# R284A.net
KiCad netlist of a schematic drawn in EAGLE
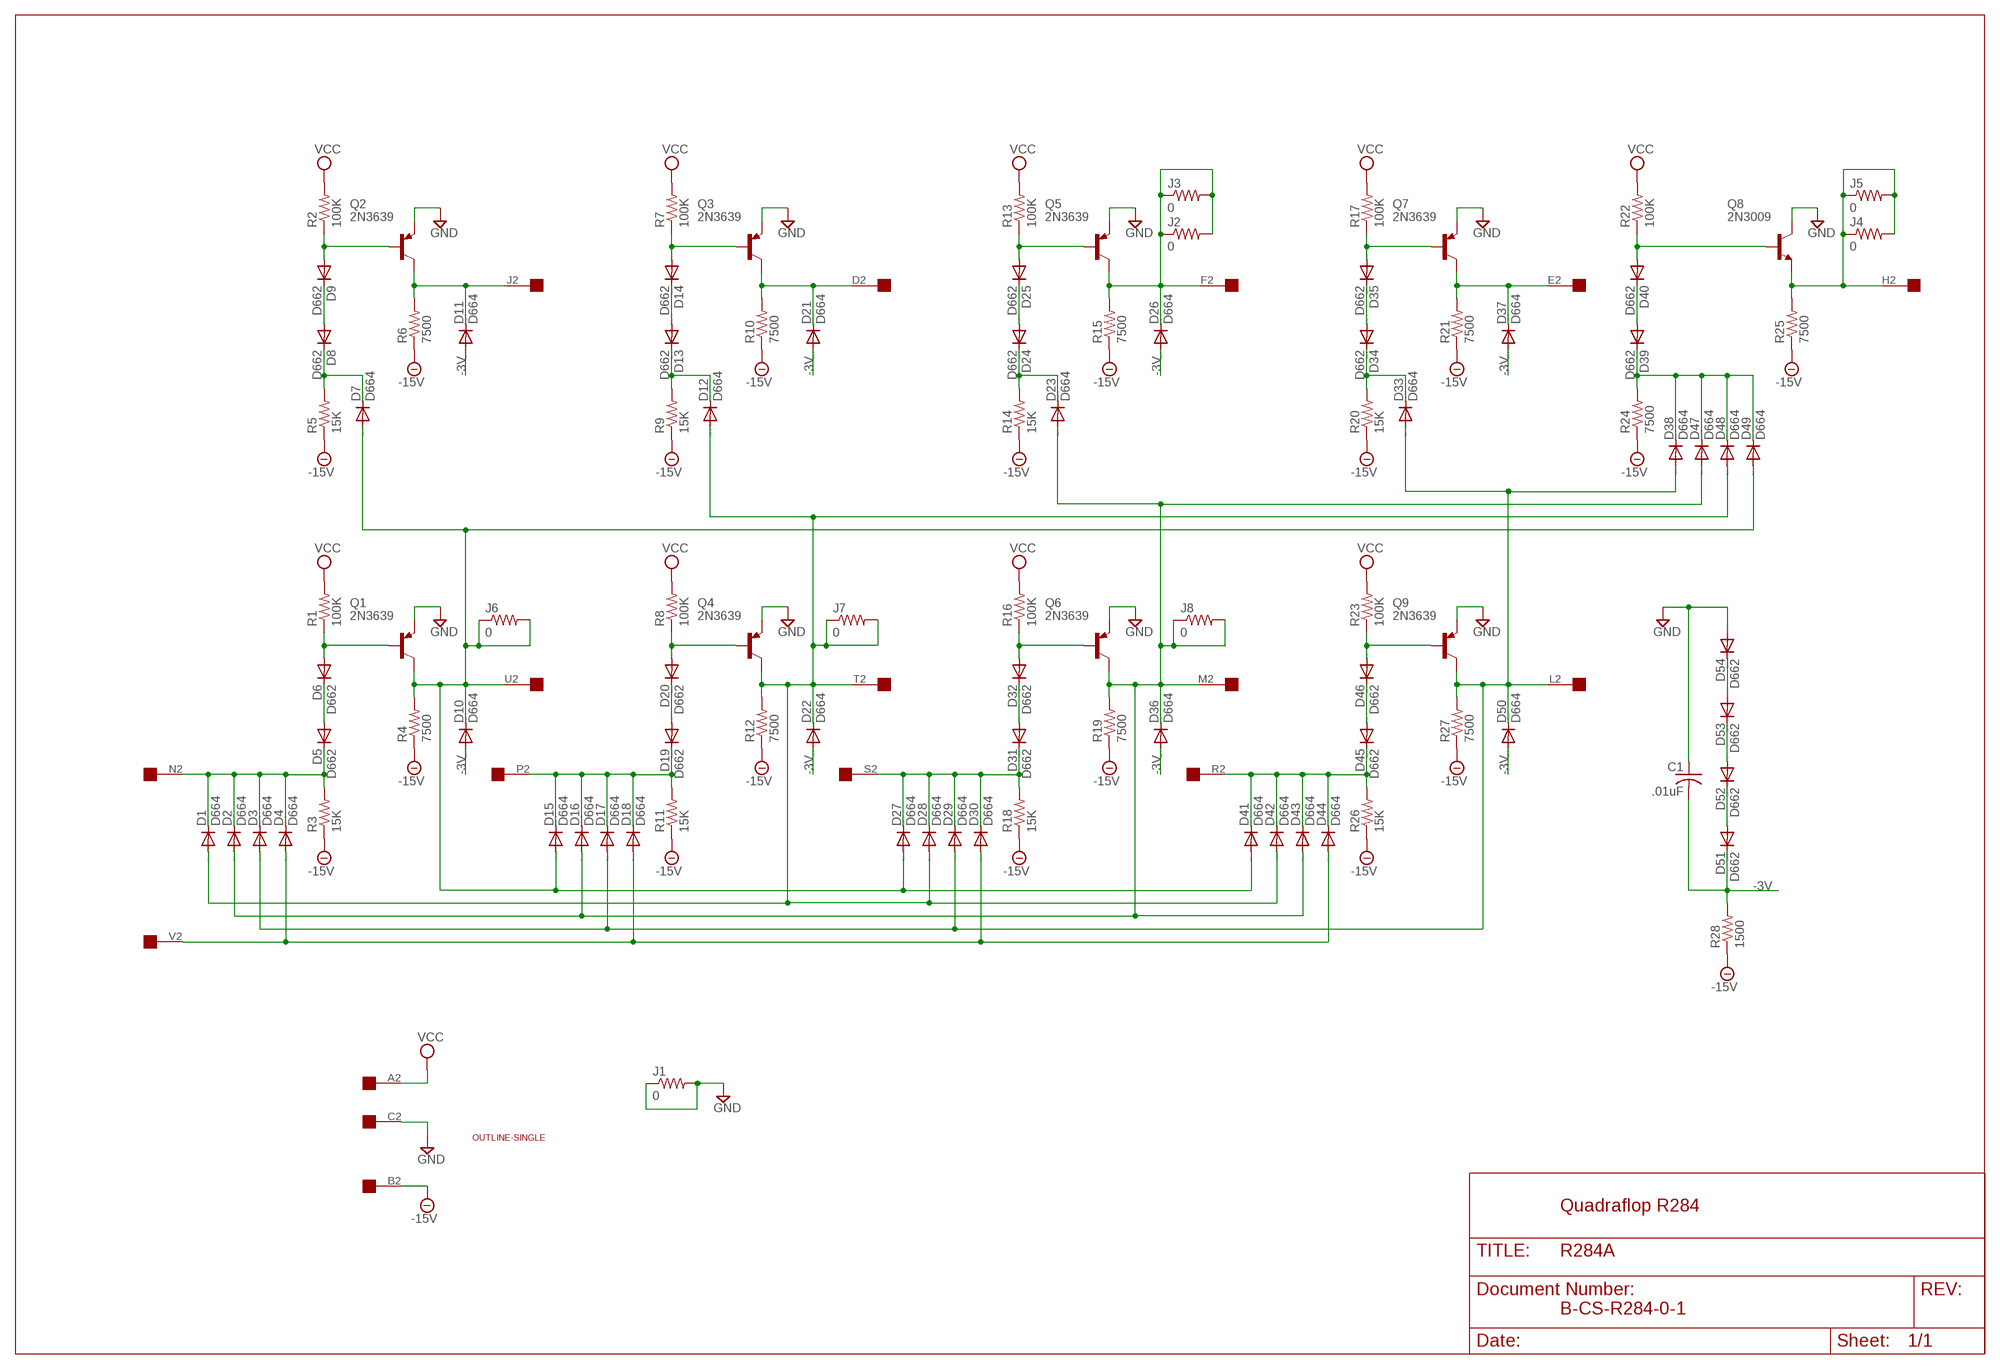
[diagram p0: schematic, sheet 1]

(export (version "E")
  (design (tool "Eeschema 10.0.6"))
  (components
    (comp (ref "C1")
      (value ".01uF")
      (footprint "eagle-import:C063-025X075")
      (libsource (lib "eagle-import") (part "C-US"))
    )
    (comp (ref "D1")
      (value "D664")
      (footprint "eagle-import:DO35-10")
      (libsource (lib "eagle-import") (part "DIODE-DO35-10"))
    )
    (comp (ref "D2")
      (value "D664")
      (footprint "eagle-import:DO35-10")
      (libsource (lib "eagle-import") (part "DIODE-DO35-10"))
    )
    (comp (ref "D3")
      (value "D664")
      (footprint "eagle-import:DO35-10")
      (libsource (lib "eagle-import") (part "DIODE-DO35-10"))
    )
    (comp (ref "D4")
      (value "D664")
      (footprint "eagle-import:DO35-10")
      (libsource (lib "eagle-import") (part "DIODE-DO35-10"))
    )
    (comp (ref "D5")
      (value "D662")
      (footprint "eagle-import:DO35-10")
      (libsource (lib "eagle-import") (part "DIODE-DO35-10"))
    )
    (comp (ref "D6")
      (value "D662")
      (footprint "eagle-import:DO35-10")
      (libsource (lib "eagle-import") (part "DIODE-DO35-10"))
    )
    (comp (ref "D7")
      (value "D664")
      (footprint "eagle-import:DO35-10")
      (libsource (lib "eagle-import") (part "DIODE-DO35-10"))
    )
    (comp (ref "D8")
      (value "D662")
      (footprint "eagle-import:DO35-10")
      (libsource (lib "eagle-import") (part "DIODE-DO35-10"))
    )
    (comp (ref "D9")
      (value "D662")
      (footprint "eagle-import:DO35-10")
      (libsource (lib "eagle-import") (part "DIODE-DO35-10"))
    )
    (comp (ref "D10")
      (value "D664")
      (footprint "eagle-import:DO35-10")
      (libsource (lib "eagle-import") (part "DIODE-DO35-10"))
    )
    (comp (ref "D11")
      (value "D664")
      (footprint "eagle-import:DO35-10")
      (libsource (lib "eagle-import") (part "DIODE-DO35-10"))
    )
    (comp (ref "D12")
      (value "D664")
      (footprint "eagle-import:DO35-10")
      (libsource (lib "eagle-import") (part "DIODE-DO35-10"))
    )
    (comp (ref "D13")
      (value "D662")
      (footprint "eagle-import:DO35-10")
      (libsource (lib "eagle-import") (part "DIODE-DO35-10"))
    )
    (comp (ref "D14")
      (value "D662")
      (footprint "eagle-import:DO35-10")
      (libsource (lib "eagle-import") (part "DIODE-DO35-10"))
    )
    (comp (ref "D15")
      (value "D664")
      (footprint "eagle-import:DO35-10")
      (libsource (lib "eagle-import") (part "DIODE-DO35-10"))
    )
    (comp (ref "D16")
      (value "D664")
      (footprint "eagle-import:DO35-10")
      (libsource (lib "eagle-import") (part "DIODE-DO35-10"))
    )
    (comp (ref "D17")
      (value "D664")
      (footprint "eagle-import:DO35-10")
      (libsource (lib "eagle-import") (part "DIODE-DO35-10"))
    )
    (comp (ref "D18")
      (value "D664")
      (footprint "eagle-import:DO35-10")
      (libsource (lib "eagle-import") (part "DIODE-DO35-10"))
    )
    (comp (ref "D19")
      (value "D662")
      (footprint "eagle-import:DO35-10")
      (libsource (lib "eagle-import") (part "DIODE-DO35-10"))
    )
    (comp (ref "D20")
      (value "D662")
      (footprint "eagle-import:DO35-10")
      (libsource (lib "eagle-import") (part "DIODE-DO35-10"))
    )
    (comp (ref "D21")
      (value "D664")
      (footprint "eagle-import:DO35-10")
      (libsource (lib "eagle-import") (part "DIODE-DO35-10"))
    )
    (comp (ref "D22")
      (value "D664")
      (footprint "eagle-import:DO35-10")
      (libsource (lib "eagle-import") (part "DIODE-DO35-10"))
    )
    (comp (ref "D23")
      (value "D664")
      (footprint "eagle-import:DO35-10")
      (libsource (lib "eagle-import") (part "DIODE-DO35-10"))
    )
    (comp (ref "D24")
      (value "D662")
      (footprint "eagle-import:DO35-10")
      (libsource (lib "eagle-import") (part "DIODE-DO35-10"))
    )
    (comp (ref "D25")
      (value "D662")
      (footprint "eagle-import:DO35-10")
      (libsource (lib "eagle-import") (part "DIODE-DO35-10"))
    )
    (comp (ref "D26")
      (value "D664")
      (footprint "eagle-import:DO35-10")
      (libsource (lib "eagle-import") (part "DIODE-DO35-10"))
    )
    (comp (ref "D27")
      (value "D664")
      (footprint "eagle-import:DO35-10")
      (libsource (lib "eagle-import") (part "DIODE-DO35-10"))
    )
    (comp (ref "D28")
      (value "D664")
      (footprint "eagle-import:DO35-10")
      (libsource (lib "eagle-import") (part "DIODE-DO35-10"))
    )
    (comp (ref "D29")
      (value "D664")
      (footprint "eagle-import:DO35-10")
      (libsource (lib "eagle-import") (part "DIODE-DO35-10"))
    )
    (comp (ref "D30")
      (value "D664")
      (footprint "eagle-import:DO35-10")
      (libsource (lib "eagle-import") (part "DIODE-DO35-10"))
    )
    (comp (ref "D31")
      (value "D662")
      (footprint "eagle-import:DO35-10")
      (libsource (lib "eagle-import") (part "DIODE-DO35-10"))
    )
    (comp (ref "D32")
      (value "D662")
      (footprint "eagle-import:DO35-10")
      (libsource (lib "eagle-import") (part "DIODE-DO35-10"))
    )
    (comp (ref "D33")
      (value "D664")
      (footprint "eagle-import:DO35-10")
      (libsource (lib "eagle-import") (part "DIODE-DO35-10"))
    )
    (comp (ref "D34")
      (value "D662")
      (footprint "eagle-import:DO35-10")
      (libsource (lib "eagle-import") (part "DIODE-DO35-10"))
    )
    (comp (ref "D35")
      (value "D662")
      (footprint "eagle-import:DO35-10")
      (libsource (lib "eagle-import") (part "DIODE-DO35-10"))
    )
    (comp (ref "D36")
      (value "D664")
      (footprint "eagle-import:DO35-10")
      (libsource (lib "eagle-import") (part "DIODE-DO35-10"))
    )
    (comp (ref "D37")
      (value "D664")
      (footprint "eagle-import:DO35-10")
      (libsource (lib "eagle-import") (part "DIODE-DO35-10"))
    )
    (comp (ref "D38")
      (value "D664")
      (footprint "eagle-import:DO35-10")
      (libsource (lib "eagle-import") (part "DIODE-DO35-10"))
    )
    (comp (ref "D39")
      (value "D662")
      (footprint "eagle-import:DO35-10")
      (libsource (lib "eagle-import") (part "DIODE-DO35-10"))
    )
    (comp (ref "D40")
      (value "D662")
      (footprint "eagle-import:DO35-10")
      (libsource (lib "eagle-import") (part "DIODE-DO35-10"))
    )
    (comp (ref "D41")
      (value "D664")
      (footprint "eagle-import:DO35-10")
      (libsource (lib "eagle-import") (part "DIODE-DO35-10"))
    )
    (comp (ref "D42")
      (value "D664")
      (footprint "eagle-import:DO35-10")
      (libsource (lib "eagle-import") (part "DIODE-DO35-10"))
    )
    (comp (ref "D43")
      (value "D664")
      (footprint "eagle-import:DO35-10")
      (libsource (lib "eagle-import") (part "DIODE-DO35-10"))
    )
    (comp (ref "D44")
      (value "D664")
      (footprint "eagle-import:DO35-10")
      (libsource (lib "eagle-import") (part "DIODE-DO35-10"))
    )
    (comp (ref "D45")
      (value "D662")
      (footprint "eagle-import:DO35-10")
      (libsource (lib "eagle-import") (part "DIODE-DO35-10"))
    )
    (comp (ref "D46")
      (value "D662")
      (footprint "eagle-import:DO35-10")
      (libsource (lib "eagle-import") (part "DIODE-DO35-10"))
    )
    (comp (ref "D47")
      (value "D664")
      (footprint "eagle-import:DO35-10")
      (libsource (lib "eagle-import") (part "DIODE-DO35-10"))
    )
    (comp (ref "D48")
      (value "D664")
      (footprint "eagle-import:DO35-10")
      (libsource (lib "eagle-import") (part "DIODE-DO35-10"))
    )
    (comp (ref "D49")
      (value "D664")
      (footprint "eagle-import:DO35-10")
      (libsource (lib "eagle-import") (part "DIODE-DO35-10"))
    )
    (comp (ref "D50")
      (value "D664")
      (footprint "eagle-import:DO35-10")
      (libsource (lib "eagle-import") (part "DIODE-DO35-10"))
    )
    (comp (ref "D51")
      (value "D662")
      (footprint "eagle-import:DO35-10")
      (libsource (lib "eagle-import") (part "DIODE-DO35-10"))
    )
    (comp (ref "D52")
      (value "D662")
      (footprint "eagle-import:DO35-10")
      (libsource (lib "eagle-import") (part "DIODE-DO35-10"))
    )
    (comp (ref "D53")
      (value "D662")
      (footprint "eagle-import:DO35-10")
      (libsource (lib "eagle-import") (part "DIODE-DO35-10"))
    )
    (comp (ref "D54")
      (value "D662")
      (footprint "eagle-import:DO35-10")
      (libsource (lib "eagle-import") (part "DIODE-DO35-10"))
    )
    (comp (ref "J1")
      (value "0")
      (footprint "eagle-import:0207_10")
      (libsource (lib "eagle-import") (part "R-US_0207/10"))
    )
    (comp (ref "J2")
      (value "0")
      (footprint "eagle-import:0207_10")
      (libsource (lib "eagle-import") (part "R-US_0207/10"))
    )
    (comp (ref "J3")
      (value "0")
      (footprint "eagle-import:0207_10")
      (libsource (lib "eagle-import") (part "R-US_0207/10"))
    )
    (comp (ref "J4")
      (value "0")
      (footprint "eagle-import:0207_10")
      (libsource (lib "eagle-import") (part "R-US_0207/10"))
    )
    (comp (ref "J5")
      (value "0")
      (footprint "eagle-import:0207_10")
      (libsource (lib "eagle-import") (part "R-US_0207/10"))
    )
    (comp (ref "J6")
      (value "0")
      (footprint "eagle-import:0207_10")
      (libsource (lib "eagle-import") (part "R-US_0207/10"))
    )
    (comp (ref "J7")
      (value "0")
      (footprint "eagle-import:0207_10")
      (libsource (lib "eagle-import") (part "R-US_0207/10"))
    )
    (comp (ref "J8")
      (value "0")
      (footprint "eagle-import:0207_10")
      (libsource (lib "eagle-import") (part "R-US_0207/10"))
    )
    (comp (ref "Q1")
      (value "2N3639")
      (footprint "eagle-import:TO5")
      (libsource (lib "eagle-import") (part "-PNP-TO5"))
    )
    (comp (ref "Q2")
      (value "2N3639")
      (footprint "eagle-import:TO5")
      (libsource (lib "eagle-import") (part "-PNP-TO5"))
    )
    (comp (ref "Q3")
      (value "2N3639")
      (footprint "eagle-import:TO5")
      (libsource (lib "eagle-import") (part "-PNP-TO5"))
    )
    (comp (ref "Q4")
      (value "2N3639")
      (footprint "eagle-import:TO5")
      (libsource (lib "eagle-import") (part "-PNP-TO5"))
    )
    (comp (ref "Q5")
      (value "2N3639")
      (footprint "eagle-import:TO5")
      (libsource (lib "eagle-import") (part "-PNP-TO5"))
    )
    (comp (ref "Q6")
      (value "2N3639")
      (footprint "eagle-import:TO5")
      (libsource (lib "eagle-import") (part "-PNP-TO5"))
    )
    (comp (ref "Q7")
      (value "2N3639")
      (footprint "eagle-import:TO5")
      (libsource (lib "eagle-import") (part "-PNP-TO5"))
    )
    (comp (ref "Q8")
      (value "2N3009")
      (footprint "eagle-import:TO5")
      (libsource (lib "eagle-import") (part "-NPN-TO5"))
    )
    (comp (ref "Q9")
      (value "2N3639")
      (footprint "eagle-import:TO5")
      (libsource (lib "eagle-import") (part "-PNP-TO5"))
    )
    (comp (ref "R1")
      (value "100K")
      (footprint "eagle-import:0207_10")
      (libsource (lib "eagle-import") (part "R-US_0207/10"))
    )
    (comp (ref "R2")
      (value "100K")
      (footprint "eagle-import:0207_10")
      (libsource (lib "eagle-import") (part "R-US_0207/10"))
    )
    (comp (ref "R3")
      (value "15K")
      (footprint "eagle-import:0207_10")
      (libsource (lib "eagle-import") (part "R-US_0207/10"))
    )
    (comp (ref "R4")
      (value "7500")
      (footprint "eagle-import:0207_10")
      (libsource (lib "eagle-import") (part "R-US_0207/10"))
    )
    (comp (ref "R5")
      (value "15K")
      (footprint "eagle-import:0207_10")
      (libsource (lib "eagle-import") (part "R-US_0207/10"))
    )
    (comp (ref "R6")
      (value "7500")
      (footprint "eagle-import:0207_10")
      (libsource (lib "eagle-import") (part "R-US_0207/10"))
    )
    (comp (ref "R7")
      (value "100K")
      (footprint "eagle-import:0207_10")
      (libsource (lib "eagle-import") (part "R-US_0207/10"))
    )
    (comp (ref "R8")
      (value "100K")
      (footprint "eagle-import:0207_10")
      (libsource (lib "eagle-import") (part "R-US_0207/10"))
    )
    (comp (ref "R9")
      (value "15K")
      (footprint "eagle-import:0207_10")
      (libsource (lib "eagle-import") (part "R-US_0207/10"))
    )
    (comp (ref "R10")
      (value "7500")
      (footprint "eagle-import:0207_10")
      (libsource (lib "eagle-import") (part "R-US_0207/10"))
    )
    (comp (ref "R11")
      (value "15K")
      (footprint "eagle-import:0207_10")
      (libsource (lib "eagle-import") (part "R-US_0207/10"))
    )
    (comp (ref "R12")
      (value "7500")
      (footprint "eagle-import:0207_10")
      (libsource (lib "eagle-import") (part "R-US_0207/10"))
    )
    (comp (ref "R13")
      (value "100K")
      (footprint "eagle-import:0207_10")
      (libsource (lib "eagle-import") (part "R-US_0207/10"))
    )
    (comp (ref "R14")
      (value "15K")
      (footprint "eagle-import:0207_10")
      (libsource (lib "eagle-import") (part "R-US_0207/10"))
    )
    (comp (ref "R15")
      (value "7500")
      (footprint "eagle-import:0207_10")
      (libsource (lib "eagle-import") (part "R-US_0207/10"))
    )
    (comp (ref "R16")
      (value "100K")
      (footprint "eagle-import:0207_10")
      (libsource (lib "eagle-import") (part "R-US_0207/10"))
    )
    (comp (ref "R17")
      (value "100K")
      (footprint "eagle-import:0207_10")
      (libsource (lib "eagle-import") (part "R-US_0207/10"))
    )
    (comp (ref "R18")
      (value "15K")
      (footprint "eagle-import:0207_10")
      (libsource (lib "eagle-import") (part "R-US_0207/10"))
    )
    (comp (ref "R19")
      (value "7500")
      (footprint "eagle-import:0207_10")
      (libsource (lib "eagle-import") (part "R-US_0207/10"))
    )
    (comp (ref "R20")
      (value "15K")
      (footprint "eagle-import:0207_10")
      (libsource (lib "eagle-import") (part "R-US_0207/10"))
    )
    (comp (ref "R21")
      (value "7500")
      (footprint "eagle-import:0207_10")
      (libsource (lib "eagle-import") (part "R-US_0207/10"))
    )
    (comp (ref "R22")
      (value "100K")
      (footprint "eagle-import:0207_10")
      (libsource (lib "eagle-import") (part "R-US_0207/10"))
    )
    (comp (ref "R23")
      (value "100K")
      (footprint "eagle-import:0207_10")
      (libsource (lib "eagle-import") (part "R-US_0207/10"))
    )
    (comp (ref "R24")
      (value "7500")
      (footprint "eagle-import:0207_10")
      (libsource (lib "eagle-import") (part "R-US_0207/10"))
    )
    (comp (ref "R25")
      (value "7500")
      (footprint "eagle-import:0207_10")
      (libsource (lib "eagle-import") (part "R-US_0207/10"))
    )
    (comp (ref "R26")
      (value "15K")
      (footprint "eagle-import:0207_10")
      (libsource (lib "eagle-import") (part "R-US_0207/10"))
    )
    (comp (ref "R27")
      (value "7500")
      (footprint "eagle-import:0207_10")
      (libsource (lib "eagle-import") (part "R-US_0207/10"))
    )
    (comp (ref "R28")
      (value "1500")
      (footprint "eagle-import:0207_10")
      (libsource (lib "eagle-import") (part "R-US_0207/10"))
    )
    (comp (ref "U$1")
      (value "OUTLINE-SINGLE")
      (footprint "eagle-import:SINGLE")
      (libsource (lib "eagle-import") (part "OUTLINE-SINGLE"))
    )
    (comp (ref "U$2")
      (value "EDGE-1")
      (footprint "eagle-import:EDGE-CON1")
      (libsource (lib "eagle-import") (part "EDGE-1"))
    )
  )
  (nets
    (net (code "1") (name "-15V") (class "Default")
      (node (ref "R10") (pin "1") (pinfunction "1_1") (pintype "passive"))
      (node (ref "R11") (pin "1") (pinfunction "1_1") (pintype "passive"))
      (node (ref "R12") (pin "1") (pinfunction "1_1") (pintype "passive"))
      (node (ref "R14") (pin "1") (pinfunction "1_1") (pintype "passive"))
      (node (ref "R15") (pin "1") (pinfunction "1_1") (pintype "passive"))
      (node (ref "R18") (pin "1") (pinfunction "1_1") (pintype "passive"))
      (node (ref "R19") (pin "1") (pinfunction "1_1") (pintype "passive"))
      (node (ref "R20") (pin "1") (pinfunction "1_1") (pintype "passive"))
      (node (ref "R21") (pin "1") (pinfunction "1_1") (pintype "passive"))
      (node (ref "R24") (pin "1") (pinfunction "1_1") (pintype "passive"))
      (node (ref "R25") (pin "1") (pinfunction "1_1") (pintype "passive"))
      (node (ref "R26") (pin "1") (pinfunction "1_1") (pintype "passive"))
      (node (ref "R27") (pin "1") (pinfunction "1_1") (pintype "passive"))
      (node (ref "R28") (pin "1") (pinfunction "1_1") (pintype "passive"))
      (node (ref "R3") (pin "1") (pinfunction "1_1") (pintype "passive"))
      (node (ref "R4") (pin "1") (pinfunction "1_1") (pintype "passive"))
      (node (ref "R5") (pin "1") (pinfunction "1_1") (pintype "passive"))
      (node (ref "R6") (pin "1") (pinfunction "1_1") (pintype "passive"))
      (node (ref "R9") (pin "1") (pinfunction "1_1") (pintype "passive"))
      (node (ref "U$2") (pin "B2") (pinfunction "1_B2") (pintype "bidirectional"))
    )
    (net (code "2") (name "/-3V") (class "Default")
      (node (ref "C1") (pin "2") (pinfunction "2_2") (pintype "passive"))
      (node (ref "D10") (pin "A") (pinfunction "A_A") (pintype "passive"))
      (node (ref "D11") (pin "A") (pinfunction "A_A") (pintype "passive"))
      (node (ref "D21") (pin "A") (pinfunction "A_A") (pintype "passive"))
      (node (ref "D22") (pin "A") (pinfunction "A_A") (pintype "passive"))
      (node (ref "D26") (pin "A") (pinfunction "A_A") (pintype "passive"))
      (node (ref "D36") (pin "A") (pinfunction "A_A") (pintype "passive"))
      (node (ref "D37") (pin "A") (pinfunction "A_A") (pintype "passive"))
      (node (ref "D50") (pin "A") (pinfunction "A_A") (pintype "passive"))
      (node (ref "D51") (pin "C") (pinfunction "C_C") (pintype "passive"))
      (node (ref "R28") (pin "2") (pinfunction "2_2") (pintype "passive"))
    )
    (net (code "3") (name "GND") (class "Default")
      (node (ref "C1") (pin "1") (pinfunction "1_1") (pintype "passive"))
      (node (ref "D54") (pin "A") (pinfunction "A_A") (pintype "passive"))
      (node (ref "J1") (pin "1") (pinfunction "1_1") (pintype "passive"))
      (node (ref "J1") (pin "2") (pinfunction "2_2") (pintype "passive"))
      (node (ref "Q1") (pin "1") (pinfunction "E_1") (pintype "passive"))
      (node (ref "Q2") (pin "1") (pinfunction "E_1") (pintype "passive"))
      (node (ref "Q3") (pin "1") (pinfunction "E_1") (pintype "passive"))
      (node (ref "Q4") (pin "1") (pinfunction "E_1") (pintype "passive"))
      (node (ref "Q5") (pin "1") (pinfunction "E_1") (pintype "passive"))
      (node (ref "Q6") (pin "1") (pinfunction "E_1") (pintype "passive"))
      (node (ref "Q7") (pin "1") (pinfunction "E_1") (pintype "passive"))
      (node (ref "Q8") (pin "3") (pinfunction "C_3") (pintype "passive"))
      (node (ref "Q9") (pin "1") (pinfunction "E_1") (pintype "passive"))
      (node (ref "U$2") (pin "C2") (pinfunction "1_C2") (pintype "bidirectional"))
    )
    (net (code "4") (name "Net-(D5-PadA)") (class "Default")
      (node (ref "D5") (pin "A") (pinfunction "A_A") (pintype "passive"))
      (node (ref "D6") (pin "C") (pinfunction "C_C") (pintype "passive"))
    )
    (net (code "5") (name "Net-(D7-PadC)") (class "Default")
      (node (ref "D7") (pin "C") (pinfunction "C_C") (pintype "passive"))
      (node (ref "D8") (pin "C") (pinfunction "C_C") (pintype "passive"))
      (node (ref "R5") (pin "2") (pinfunction "2_2") (pintype "passive"))
    )
    (net (code "6") (name "Net-(D8-PadA)") (class "Default")
      (node (ref "D8") (pin "A") (pinfunction "A_A") (pintype "passive"))
      (node (ref "D9") (pin "C") (pinfunction "C_C") (pintype "passive"))
    )
    (net (code "7") (name "Net-(D12-PadC)") (class "Default")
      (node (ref "D12") (pin "C") (pinfunction "C_C") (pintype "passive"))
      (node (ref "D13") (pin "C") (pinfunction "C_C") (pintype "passive"))
      (node (ref "R9") (pin "2") (pinfunction "2_2") (pintype "passive"))
    )
    (net (code "8") (name "Net-(D13-PadA)") (class "Default")
      (node (ref "D13") (pin "A") (pinfunction "A_A") (pintype "passive"))
      (node (ref "D14") (pin "C") (pinfunction "C_C") (pintype "passive"))
    )
    (net (code "9") (name "Net-(D19-PadA)") (class "Default")
      (node (ref "D19") (pin "A") (pinfunction "A_A") (pintype "passive"))
      (node (ref "D20") (pin "C") (pinfunction "C_C") (pintype "passive"))
    )
    (net (code "10") (name "Net-(D23-PadC)") (class "Default")
      (node (ref "D23") (pin "C") (pinfunction "C_C") (pintype "passive"))
      (node (ref "D24") (pin "C") (pinfunction "C_C") (pintype "passive"))
      (node (ref "R14") (pin "2") (pinfunction "2_2") (pintype "passive"))
    )
    (net (code "11") (name "Net-(D24-PadA)") (class "Default")
      (node (ref "D24") (pin "A") (pinfunction "A_A") (pintype "passive"))
      (node (ref "D25") (pin "C") (pinfunction "C_C") (pintype "passive"))
    )
    (net (code "12") (name "Net-(D31-PadA)") (class "Default")
      (node (ref "D31") (pin "A") (pinfunction "A_A") (pintype "passive"))
      (node (ref "D32") (pin "C") (pinfunction "C_C") (pintype "passive"))
    )
    (net (code "13") (name "Net-(D33-PadC)") (class "Default")
      (node (ref "D33") (pin "C") (pinfunction "C_C") (pintype "passive"))
      (node (ref "D34") (pin "C") (pinfunction "C_C") (pintype "passive"))
      (node (ref "R20") (pin "2") (pinfunction "2_2") (pintype "passive"))
    )
    (net (code "14") (name "Net-(D34-PadA)") (class "Default")
      (node (ref "D34") (pin "A") (pinfunction "A_A") (pintype "passive"))
      (node (ref "D35") (pin "C") (pinfunction "C_C") (pintype "passive"))
    )
    (net (code "15") (name "Net-(D38-PadC)") (class "Default")
      (node (ref "D38") (pin "C") (pinfunction "C_C") (pintype "passive"))
      (node (ref "D39") (pin "C") (pinfunction "C_C") (pintype "passive"))
      (node (ref "D47") (pin "C") (pinfunction "C_C") (pintype "passive"))
      (node (ref "D48") (pin "C") (pinfunction "C_C") (pintype "passive"))
      (node (ref "D49") (pin "C") (pinfunction "C_C") (pintype "passive"))
      (node (ref "R24") (pin "2") (pinfunction "2_2") (pintype "passive"))
    )
    (net (code "16") (name "Net-(D39-PadA)") (class "Default")
      (node (ref "D39") (pin "A") (pinfunction "A_A") (pintype "passive"))
      (node (ref "D40") (pin "C") (pinfunction "C_C") (pintype "passive"))
    )
    (net (code "17") (name "Net-(D45-PadA)") (class "Default")
      (node (ref "D45") (pin "A") (pinfunction "A_A") (pintype "passive"))
      (node (ref "D46") (pin "C") (pinfunction "C_C") (pintype "passive"))
    )
    (net (code "18") (name "Net-(D51-PadA)") (class "Default")
      (node (ref "D51") (pin "A") (pinfunction "A_A") (pintype "passive"))
      (node (ref "D52") (pin "C") (pinfunction "C_C") (pintype "passive"))
    )
    (net (code "19") (name "Net-(D52-PadA)") (class "Default")
      (node (ref "D52") (pin "A") (pinfunction "A_A") (pintype "passive"))
      (node (ref "D53") (pin "C") (pinfunction "C_C") (pintype "passive"))
    )
    (net (code "20") (name "Net-(D53-PadA)") (class "Default")
      (node (ref "D53") (pin "A") (pinfunction "A_A") (pintype "passive"))
      (node (ref "D54") (pin "C") (pinfunction "C_C") (pintype "passive"))
    )
    (net (code "21") (name "Net-(Q1-B)") (class "Default")
      (node (ref "D6") (pin "A") (pinfunction "A_A") (pintype "passive"))
      (node (ref "Q1") (pin "2") (pinfunction "B_2") (pintype "passive"))
      (node (ref "R1") (pin "1") (pinfunction "1_1") (pintype "passive"))
    )
    (net (code "22") (name "Net-(Q1-C)") (class "Default")
      (node (ref "D10") (pin "C") (pinfunction "C_C") (pintype "passive"))
      (node (ref "D15") (pin "A") (pinfunction "A_A") (pintype "passive"))
      (node (ref "D27") (pin "A") (pinfunction "A_A") (pintype "passive"))
      (node (ref "D41") (pin "A") (pinfunction "A_A") (pintype "passive"))
      (node (ref "D49") (pin "A") (pinfunction "A_A") (pintype "passive"))
      (node (ref "D7") (pin "A") (pinfunction "A_A") (pintype "passive"))
      (node (ref "J6") (pin "1") (pinfunction "1_1") (pintype "passive"))
      (node (ref "J6") (pin "2") (pinfunction "2_2") (pintype "passive"))
      (node (ref "Q1") (pin "3") (pinfunction "C_3") (pintype "passive"))
      (node (ref "R4") (pin "2") (pinfunction "2_2") (pintype "passive"))
      (node (ref "U$2") (pin "U2") (pinfunction "1_U2") (pintype "bidirectional"))
    )
    (net (code "23") (name "Net-(Q2-B)") (class "Default")
      (node (ref "D9") (pin "A") (pinfunction "A_A") (pintype "passive"))
      (node (ref "Q2") (pin "2") (pinfunction "B_2") (pintype "passive"))
      (node (ref "R2") (pin "1") (pinfunction "1_1") (pintype "passive"))
    )
    (net (code "24") (name "Net-(Q2-C)") (class "Default")
      (node (ref "D11") (pin "C") (pinfunction "C_C") (pintype "passive"))
      (node (ref "Q2") (pin "3") (pinfunction "C_3") (pintype "passive"))
      (node (ref "R6") (pin "2") (pinfunction "2_2") (pintype "passive"))
      (node (ref "U$2") (pin "J2") (pinfunction "1_J2") (pintype "bidirectional"))
    )
    (net (code "25") (name "Net-(Q3-B)") (class "Default")
      (node (ref "D14") (pin "A") (pinfunction "A_A") (pintype "passive"))
      (node (ref "Q3") (pin "2") (pinfunction "B_2") (pintype "passive"))
      (node (ref "R7") (pin "1") (pinfunction "1_1") (pintype "passive"))
    )
    (net (code "26") (name "Net-(Q3-C)") (class "Default")
      (node (ref "D21") (pin "C") (pinfunction "C_C") (pintype "passive"))
      (node (ref "Q3") (pin "3") (pinfunction "C_3") (pintype "passive"))
      (node (ref "R10") (pin "2") (pinfunction "2_2") (pintype "passive"))
      (node (ref "U$2") (pin "D2") (pinfunction "1_D2") (pintype "bidirectional"))
    )
    (net (code "27") (name "Net-(Q4-B)") (class "Default")
      (node (ref "D20") (pin "A") (pinfunction "A_A") (pintype "passive"))
      (node (ref "Q4") (pin "2") (pinfunction "B_2") (pintype "passive"))
      (node (ref "R8") (pin "1") (pinfunction "1_1") (pintype "passive"))
    )
    (net (code "28") (name "Net-(Q4-C)") (class "Default")
      (node (ref "D1") (pin "A") (pinfunction "A_A") (pintype "passive"))
      (node (ref "D12") (pin "A") (pinfunction "A_A") (pintype "passive"))
      (node (ref "D22") (pin "C") (pinfunction "C_C") (pintype "passive"))
      (node (ref "D28") (pin "A") (pinfunction "A_A") (pintype "passive"))
      (node (ref "D42") (pin "A") (pinfunction "A_A") (pintype "passive"))
      (node (ref "D48") (pin "A") (pinfunction "A_A") (pintype "passive"))
      (node (ref "J7") (pin "1") (pinfunction "1_1") (pintype "passive"))
      (node (ref "J7") (pin "2") (pinfunction "2_2") (pintype "passive"))
      (node (ref "Q4") (pin "3") (pinfunction "C_3") (pintype "passive"))
      (node (ref "R12") (pin "2") (pinfunction "2_2") (pintype "passive"))
      (node (ref "U$2") (pin "T2") (pinfunction "1_T2") (pintype "bidirectional"))
    )
    (net (code "29") (name "Net-(Q5-B)") (class "Default")
      (node (ref "D25") (pin "A") (pinfunction "A_A") (pintype "passive"))
      (node (ref "Q5") (pin "2") (pinfunction "B_2") (pintype "passive"))
      (node (ref "R13") (pin "1") (pinfunction "1_1") (pintype "passive"))
    )
    (net (code "30") (name "Net-(Q5-C)") (class "Default")
      (node (ref "D26") (pin "C") (pinfunction "C_C") (pintype "passive"))
      (node (ref "J2") (pin "1") (pinfunction "1_1") (pintype "passive"))
      (node (ref "J2") (pin "2") (pinfunction "2_2") (pintype "passive"))
      (node (ref "J3") (pin "1") (pinfunction "1_1") (pintype "passive"))
      (node (ref "J3") (pin "2") (pinfunction "2_2") (pintype "passive"))
      (node (ref "Q5") (pin "3") (pinfunction "C_3") (pintype "passive"))
      (node (ref "R15") (pin "2") (pinfunction "2_2") (pintype "passive"))
      (node (ref "U$2") (pin "F2") (pinfunction "1_F2") (pintype "bidirectional"))
    )
    (net (code "31") (name "Net-(Q6-B)") (class "Default")
      (node (ref "D32") (pin "A") (pinfunction "A_A") (pintype "passive"))
      (node (ref "Q6") (pin "2") (pinfunction "B_2") (pintype "passive"))
      (node (ref "R16") (pin "1") (pinfunction "1_1") (pintype "passive"))
    )
    (net (code "32") (name "Net-(Q6-C)") (class "Default")
      (node (ref "D16") (pin "A") (pinfunction "A_A") (pintype "passive"))
      (node (ref "D2") (pin "A") (pinfunction "A_A") (pintype "passive"))
      (node (ref "D23") (pin "A") (pinfunction "A_A") (pintype "passive"))
      (node (ref "D36") (pin "C") (pinfunction "C_C") (pintype "passive"))
      (node (ref "D43") (pin "A") (pinfunction "A_A") (pintype "passive"))
      (node (ref "D47") (pin "A") (pinfunction "A_A") (pintype "passive"))
      (node (ref "J8") (pin "1") (pinfunction "1_1") (pintype "passive"))
      (node (ref "J8") (pin "2") (pinfunction "2_2") (pintype "passive"))
      (node (ref "Q6") (pin "3") (pinfunction "C_3") (pintype "passive"))
      (node (ref "R19") (pin "2") (pinfunction "2_2") (pintype "passive"))
      (node (ref "U$2") (pin "M2") (pinfunction "1_M2") (pintype "bidirectional"))
    )
    (net (code "33") (name "Net-(Q7-B)") (class "Default")
      (node (ref "D35") (pin "A") (pinfunction "A_A") (pintype "passive"))
      (node (ref "Q7") (pin "2") (pinfunction "B_2") (pintype "passive"))
      (node (ref "R17") (pin "1") (pinfunction "1_1") (pintype "passive"))
    )
    (net (code "34") (name "Net-(Q7-C)") (class "Default")
      (node (ref "D37") (pin "C") (pinfunction "C_C") (pintype "passive"))
      (node (ref "Q7") (pin "3") (pinfunction "C_3") (pintype "passive"))
      (node (ref "R21") (pin "2") (pinfunction "2_2") (pintype "passive"))
      (node (ref "U$2") (pin "E2") (pinfunction "1_E2") (pintype "bidirectional"))
    )
    (net (code "35") (name "Net-(Q8-B)") (class "Default")
      (node (ref "D40") (pin "A") (pinfunction "A_A") (pintype "passive"))
      (node (ref "Q8") (pin "2") (pinfunction "B_2") (pintype "passive"))
      (node (ref "R22") (pin "1") (pinfunction "1_1") (pintype "passive"))
    )
    (net (code "36") (name "Net-(Q8-E)") (class "Default")
      (node (ref "J4") (pin "1") (pinfunction "1_1") (pintype "passive"))
      (node (ref "J4") (pin "2") (pinfunction "2_2") (pintype "passive"))
      (node (ref "J5") (pin "1") (pinfunction "1_1") (pintype "passive"))
      (node (ref "J5") (pin "2") (pinfunction "2_2") (pintype "passive"))
      (node (ref "Q8") (pin "1") (pinfunction "E_1") (pintype "passive"))
      (node (ref "R25") (pin "2") (pinfunction "2_2") (pintype "passive"))
      (node (ref "U$2") (pin "H2") (pinfunction "1_H2") (pintype "bidirectional"))
    )
    (net (code "37") (name "Net-(Q9-B)") (class "Default")
      (node (ref "D46") (pin "A") (pinfunction "A_A") (pintype "passive"))
      (node (ref "Q9") (pin "2") (pinfunction "B_2") (pintype "passive"))
      (node (ref "R23") (pin "1") (pinfunction "1_1") (pintype "passive"))
    )
    (net (code "38") (name "Net-(Q9-C)") (class "Default")
      (node (ref "D17") (pin "A") (pinfunction "A_A") (pintype "passive"))
      (node (ref "D29") (pin "A") (pinfunction "A_A") (pintype "passive"))
      (node (ref "D3") (pin "A") (pinfunction "A_A") (pintype "passive"))
      (node (ref "D33") (pin "A") (pinfunction "A_A") (pintype "passive"))
      (node (ref "D38") (pin "A") (pinfunction "A_A") (pintype "passive"))
      (node (ref "D50") (pin "C") (pinfunction "C_C") (pintype "passive"))
      (node (ref "Q9") (pin "3") (pinfunction "C_3") (pintype "passive"))
      (node (ref "R27") (pin "2") (pinfunction "2_2") (pintype "passive"))
      (node (ref "U$2") (pin "L2") (pinfunction "1_L2") (pintype "bidirectional"))
    )
    (net (code "39") (name "Net-(U$2L-1)") (class "Default")
      (node (ref "D1") (pin "C") (pinfunction "C_C") (pintype "passive"))
      (node (ref "D2") (pin "C") (pinfunction "C_C") (pintype "passive"))
      (node (ref "D3") (pin "C") (pinfunction "C_C") (pintype "passive"))
      (node (ref "D4") (pin "C") (pinfunction "C_C") (pintype "passive"))
      (node (ref "D5") (pin "C") (pinfunction "C_C") (pintype "passive"))
      (node (ref "R3") (pin "2") (pinfunction "2_2") (pintype "passive"))
      (node (ref "U$2") (pin "N2") (pinfunction "1_N2") (pintype "bidirectional"))
    )
    (net (code "40") (name "Net-(U$2M-1)") (class "Default")
      (node (ref "D15") (pin "C") (pinfunction "C_C") (pintype "passive"))
      (node (ref "D16") (pin "C") (pinfunction "C_C") (pintype "passive"))
      (node (ref "D17") (pin "C") (pinfunction "C_C") (pintype "passive"))
      (node (ref "D18") (pin "C") (pinfunction "C_C") (pintype "passive"))
      (node (ref "D19") (pin "C") (pinfunction "C_C") (pintype "passive"))
      (node (ref "R11") (pin "2") (pinfunction "2_2") (pintype "passive"))
      (node (ref "U$2") (pin "P2") (pinfunction "1_P2") (pintype "bidirectional"))
    )
    (net (code "41") (name "Net-(U$2N-1)") (class "Default")
      (node (ref "D41") (pin "C") (pinfunction "C_C") (pintype "passive"))
      (node (ref "D42") (pin "C") (pinfunction "C_C") (pintype "passive"))
      (node (ref "D43") (pin "C") (pinfunction "C_C") (pintype "passive"))
      (node (ref "D44") (pin "C") (pinfunction "C_C") (pintype "passive"))
      (node (ref "D45") (pin "C") (pinfunction "C_C") (pintype "passive"))
      (node (ref "R26") (pin "2") (pinfunction "2_2") (pintype "passive"))
      (node (ref "U$2") (pin "R2") (pinfunction "1_R2") (pintype "bidirectional"))
    )
    (net (code "42") (name "Net-(U$2O-1)") (class "Default")
      (node (ref "D27") (pin "C") (pinfunction "C_C") (pintype "passive"))
      (node (ref "D28") (pin "C") (pinfunction "C_C") (pintype "passive"))
      (node (ref "D29") (pin "C") (pinfunction "C_C") (pintype "passive"))
      (node (ref "D30") (pin "C") (pinfunction "C_C") (pintype "passive"))
      (node (ref "D31") (pin "C") (pinfunction "C_C") (pintype "passive"))
      (node (ref "R18") (pin "2") (pinfunction "2_2") (pintype "passive"))
      (node (ref "U$2") (pin "S2") (pinfunction "1_S2") (pintype "bidirectional"))
    )
    (net (code "43") (name "Net-(U$2R-1)") (class "Default")
      (node (ref "D18") (pin "A") (pinfunction "A_A") (pintype "passive"))
      (node (ref "D30") (pin "A") (pinfunction "A_A") (pintype "passive"))
      (node (ref "D4") (pin "A") (pinfunction "A_A") (pintype "passive"))
      (node (ref "D44") (pin "A") (pinfunction "A_A") (pintype "passive"))
      (node (ref "U$2") (pin "V2") (pinfunction "1_V2") (pintype "bidirectional"))
    )
    (net (code "44") (name "VCC") (class "Default")
      (node (ref "R1") (pin "2") (pinfunction "2_2") (pintype "passive"))
      (node (ref "R13") (pin "2") (pinfunction "2_2") (pintype "passive"))
      (node (ref "R16") (pin "2") (pinfunction "2_2") (pintype "passive"))
      (node (ref "R17") (pin "2") (pinfunction "2_2") (pintype "passive"))
      (node (ref "R2") (pin "2") (pinfunction "2_2") (pintype "passive"))
      (node (ref "R22") (pin "2") (pinfunction "2_2") (pintype "passive"))
      (node (ref "R23") (pin "2") (pinfunction "2_2") (pintype "passive"))
      (node (ref "R7") (pin "2") (pinfunction "2_2") (pintype "passive"))
      (node (ref "R8") (pin "2") (pinfunction "2_2") (pintype "passive"))
      (node (ref "U$2") (pin "A2") (pinfunction "1_A2") (pintype "bidirectional"))
    )
  )
)
